# Pulleyboard.net
KiCad netlist of a schematic drawn in EAGLE
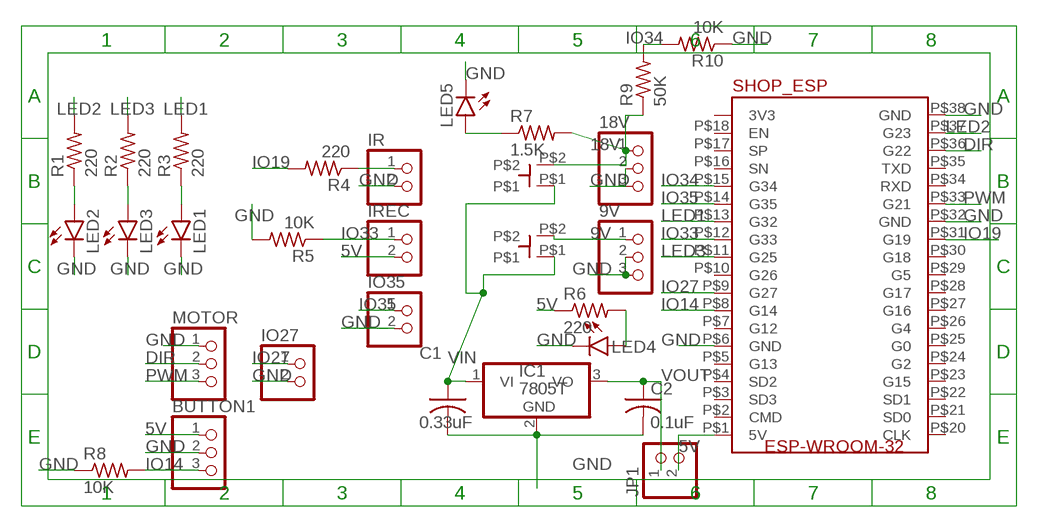
[diagram p0: schematic, sheet 1]

(export (version "E")
  (design (tool "Eeschema 10.0.6"))
  (components
    (comp (ref "9V")
      (value "PINHD-1X3")
      (footprint "eagle-import:1X03")
      (libsource (lib "eagle-import") (part "PINHD-1X3"))
    )
    (comp (ref "9VSW")
      (value "SWITCH")
      (footprint "eagle-import:SWTICH")
      (fields (field (name "SPICEPREFIX") "B"))
      (libsource (lib "eagle-import") (part "SWITCH"))
    )
    (comp (ref "18V")
      (value "PINHD-1X3")
      (footprint "eagle-import:1X03")
      (libsource (lib "eagle-import") (part "PINHD-1X3"))
    )
    (comp (ref "18VSW")
      (value "SWITCH")
      (footprint "eagle-import:SWTICH")
      (libsource (lib "eagle-import") (part "SWITCH"))
    )
    (comp (ref "BUTTON1")
      (value "PINHD-1X3")
      (footprint "eagle-import:1X03")
      (libsource (lib "eagle-import") (part "PINHD-1X3"))
    )
    (comp (ref "C1")
      (value "0.33uF")
      (footprint "eagle-import:C025-030X050")
      (libsource (lib "eagle-import") (part "C-US025-030X050"))
    )
    (comp (ref "C2")
      (value "0.1uF")
      (footprint "eagle-import:C025-030X050")
      (libsource (lib "eagle-import") (part "C-US025-030X050"))
    )
    (comp (ref "IC1")
      (value "7805T")
      (footprint "eagle-import:TO220H")
      (libsource (lib "eagle-import") (part "78T05"))
    )
    (comp (ref "IO27")
      (value "PINHD-1X2")
      (footprint "eagle-import:1X02")
      (libsource (lib "eagle-import") (part "PINHD-1X2"))
    )
    (comp (ref "IO35")
      (value "PINHD-1X2")
      (footprint "eagle-import:1X02")
      (libsource (lib "eagle-import") (part "PINHD-1X2"))
    )
    (comp (ref "IR")
      (value "PINHD-1X2")
      (footprint "eagle-import:1X02")
      (libsource (lib "eagle-import") (part "PINHD-1X2"))
    )
    (comp (ref "IREC")
      (value "PINHD-1X2")
      (footprint "eagle-import:1X02")
      (libsource (lib "eagle-import") (part "PINHD-1X2"))
    )
    (comp (ref "JP1")
      (value "PINHD-1X2")
      (footprint "eagle-import:1X02")
      (libsource (lib "eagle-import") (part "PINHD-1X2"))
    )
    (comp (ref "LED1")
      (value "LED5MM")
      (footprint "eagle-import:LED5MM")
      (libsource (lib "eagle-import") (part "ledbighole_LED5MM"))
    )
    (comp (ref "LED2")
      (value "LED5MM")
      (footprint "eagle-import:LED5MM")
      (libsource (lib "eagle-import") (part "ledbighole_LED5MM"))
    )
    (comp (ref "LED3")
      (value "LED5MM")
      (footprint "eagle-import:LED5MM")
      (libsource (lib "eagle-import") (part "ledbighole_LED5MM"))
    )
    (comp (ref "LED4")
      (value "LEDCHIPLED_1206")
      (footprint "eagle-import:CHIPLED_1206")
      (libsource (lib "eagle-import") (part "LEDCHIPLED_1206"))
    )
    (comp (ref "LED5")
      (value "LED5MM")
      (footprint "eagle-import:LED5MM")
      (libsource (lib "eagle-import") (part "ledbighole_LED5MM"))
    )
    (comp (ref "MOTOR")
      (value "PINHD-1X3")
      (footprint "eagle-import:1X03")
      (libsource (lib "eagle-import") (part "PINHD-1X3"))
    )
    (comp (ref "R1")
      (value "220")
      (footprint "eagle-import:R0805")
      (libsource (lib "eagle-import") (part "R-US_R0805"))
    )
    (comp (ref "R2")
      (value "220")
      (footprint "eagle-import:R0805")
      (libsource (lib "eagle-import") (part "R-US_R0805"))
    )
    (comp (ref "R3")
      (value "220")
      (footprint "eagle-import:R0805")
      (libsource (lib "eagle-import") (part "R-US_R0805"))
    )
    (comp (ref "R4")
      (value "220")
      (footprint "eagle-import:R0805")
      (libsource (lib "eagle-import") (part "R-US_R0805"))
    )
    (comp (ref "R5")
      (value "10K")
      (footprint "eagle-import:R0805")
      (libsource (lib "eagle-import") (part "R-US_R0805"))
    )
    (comp (ref "R6")
      (value "220")
      (footprint "eagle-import:R0805")
      (libsource (lib "eagle-import") (part "R-US_R0805"))
    )
    (comp (ref "R7")
      (value "1.5K")
      (footprint "eagle-import:R0805")
      (libsource (lib "eagle-import") (part "R-US_R0805"))
    )
    (comp (ref "R8")
      (value "10K")
      (footprint "eagle-import:R0805")
      (libsource (lib "eagle-import") (part "R-US_R0805"))
    )
    (comp (ref "R9")
      (value "50K")
      (footprint "eagle-import:R0805")
      (libsource (lib "eagle-import") (part "R-US_R0805"))
    )
    (comp (ref "R10")
      (value "10K")
      (footprint "eagle-import:R0805")
      (libsource (lib "eagle-import") (part "R-US_R0805"))
    )
    (comp (ref "U$3")
      (value "SHOP_ESP")
      (footprint "eagle-import:ESP32-WROOM-32")
      (libsource (lib "eagle-import") (part "SHOP_ESP"))
    )
  )
  (nets
    (net (code "1") (name "/3V3") (class "Default")
      (node (ref "U$3") (pin "P$19") (pinfunction "3V3_P$19") (pintype "power_in"))
    )
    (net (code "2") (name "/5V") (class "Default")
      (node (ref "BUTTON1") (pin "1") (pinfunction "1_1") (pintype "passive"))
      (node (ref "IREC") (pin "2") (pinfunction "2_2") (pintype "passive"))
      (node (ref "JP1") (pin "2") (pinfunction "2_2") (pintype "passive"))
      (node (ref "R6") (pin "1") (pinfunction "1_1") (pintype "passive"))
      (node (ref "U$3") (pin "P$1") (pinfunction "5V_P$1") (pintype "power_in"))
    )
    (net (code "3") (name "/9V") (class "Default")
      (node (ref "9V") (pin "1") (pinfunction "1_1") (pintype "passive"))
      (node (ref "9VSW") (pin "P$2") (pinfunction "P$2_P$2") (pintype "bidirectional"))
    )
    (net (code "4") (name "/18V") (class "Default")
      (node (ref "18V") (pin "1") (pinfunction "1_1") (pintype "passive"))
      (node (ref "18VSW") (pin "P$2") (pinfunction "P$2_P$2") (pintype "bidirectional"))
      (node (ref "R7") (pin "2") (pinfunction "2_2") (pintype "passive"))
      (node (ref "R9") (pin "1") (pinfunction "1_1") (pintype "passive"))
    )
    (net (code "5") (name "/CMD") (class "Default")
      (node (ref "U$3") (pin "P$2") (pinfunction "CMD_P$2") (pintype "power_in"))
    )
    (net (code "6") (name "/DIR") (class "Default")
      (node (ref "MOTOR") (pin "2") (pinfunction "2_2") (pintype "passive"))
      (node (ref "U$3") (pin "P$36") (pinfunction "G22_P$36") (pintype "bidirectional"))
    )
    (net (code "7") (name "/GND") (class "Default")
      (node (ref "18V") (pin "2") (pinfunction "2_2") (pintype "passive"))
      (node (ref "18V") (pin "3") (pinfunction "3_3") (pintype "passive"))
      (node (ref "9V") (pin "2") (pinfunction "2_2") (pintype "passive"))
      (node (ref "9V") (pin "3") (pinfunction "3_3") (pintype "passive"))
      (node (ref "BUTTON1") (pin "2") (pinfunction "2_2") (pintype "passive"))
      (node (ref "C1") (pin "2") (pinfunction "2_2") (pintype "passive"))
      (node (ref "C2") (pin "2") (pinfunction "2_2") (pintype "passive"))
      (node (ref "IC1") (pin "2") (pinfunction "GND_2") (pintype "passive"))
      (node (ref "IO27") (pin "2") (pinfunction "2_2") (pintype "passive"))
      (node (ref "IO35") (pin "2") (pinfunction "2_2") (pintype "passive"))
      (node (ref "IR") (pin "2") (pinfunction "2_2") (pintype "passive"))
      (node (ref "LED1") (pin "K") (pinfunction "C_K") (pintype "passive"))
      (node (ref "LED2") (pin "K") (pinfunction "C_K") (pintype "passive"))
      (node (ref "LED3") (pin "K") (pinfunction "C_K") (pintype "passive"))
      (node (ref "LED4") (pin "C") (pinfunction "C_C") (pintype "passive"))
      (node (ref "LED5") (pin "K") (pinfunction "C_K") (pintype "passive"))
      (node (ref "MOTOR") (pin "1") (pinfunction "1_1") (pintype "passive"))
      (node (ref "R10") (pin "1") (pinfunction "1_1") (pintype "passive"))
      (node (ref "R5") (pin "2") (pinfunction "2_2") (pintype "passive"))
      (node (ref "R8") (pin "1") (pinfunction "1_1") (pintype "passive"))
      (node (ref "U$3") (pin "P$32") (pinfunction "GND_P$32") (pintype "bidirectional"))
      (node (ref "U$3") (pin "P$38") (pinfunction "GND_P$38") (pintype "bidirectional"))
      (node (ref "U$3") (pin "P$6") (pinfunction "GND_P$6") (pintype "bidirectional"))
    )
    (net (code "8") (name "/IO14") (class "Default")
      (node (ref "BUTTON1") (pin "3") (pinfunction "3_3") (pintype "passive"))
      (node (ref "R8") (pin "2") (pinfunction "2_2") (pintype "passive"))
      (node (ref "U$3") (pin "P$8") (pinfunction "G14_P$8") (pintype "bidirectional"))
    )
    (net (code "9") (name "/IO19") (class "Default")
      (node (ref "R4") (pin "2") (pinfunction "2_2") (pintype "passive"))
      (node (ref "U$3") (pin "P$31") (pinfunction "G19_P$31") (pintype "bidirectional"))
    )
    (net (code "10") (name "/IO27") (class "Default")
      (node (ref "IO27") (pin "1") (pinfunction "1_1") (pintype "passive"))
      (node (ref "U$3") (pin "P$9") (pinfunction "G27_P$9") (pintype "bidirectional"))
    )
    (net (code "11") (name "/IO33") (class "Default")
      (node (ref "IREC") (pin "1") (pinfunction "1_1") (pintype "passive"))
      (node (ref "R5") (pin "1") (pinfunction "1_1") (pintype "passive"))
      (node (ref "U$3") (pin "P$12") (pinfunction "G33_P$12") (pintype "bidirectional"))
    )
    (net (code "12") (name "/IO34") (class "Default")
      (node (ref "R10") (pin "2") (pinfunction "2_2") (pintype "passive"))
      (node (ref "R9") (pin "2") (pinfunction "2_2") (pintype "passive"))
      (node (ref "U$3") (pin "P$15") (pinfunction "G34_P$15") (pintype "bidirectional"))
    )
    (net (code "13") (name "/IO35") (class "Default")
      (node (ref "IO35") (pin "1") (pinfunction "1_1") (pintype "passive"))
      (node (ref "U$3") (pin "P$14") (pinfunction "G35_P$14") (pintype "bidirectional"))
    )
    (net (code "14") (name "/LED1") (class "Default")
      (node (ref "R3") (pin "2") (pinfunction "2_2") (pintype "passive"))
      (node (ref "U$3") (pin "P$13") (pinfunction "G32_P$13") (pintype "bidirectional"))
    )
    (net (code "15") (name "/LED2") (class "Default")
      (node (ref "R1") (pin "2") (pinfunction "2_2") (pintype "passive"))
      (node (ref "U$3") (pin "P$37") (pinfunction "G23_P$37") (pintype "bidirectional"))
    )
    (net (code "16") (name "/LED3") (class "Default")
      (node (ref "R2") (pin "2") (pinfunction "2_2") (pintype "passive"))
      (node (ref "U$3") (pin "P$11") (pinfunction "G25_P$11") (pintype "bidirectional"))
    )
    (net (code "17") (name "/PWM") (class "Default")
      (node (ref "MOTOR") (pin "3") (pinfunction "3_3") (pintype "passive"))
      (node (ref "U$3") (pin "P$33") (pinfunction "G21_P$33") (pintype "bidirectional"))
    )
    (net (code "18") (name "/VIN") (class "Default")
      (node (ref "18VSW") (pin "P$1") (pinfunction "P$1_P$1") (pintype "bidirectional"))
      (node (ref "9VSW") (pin "P$1") (pinfunction "P$1_P$1") (pintype "bidirectional"))
      (node (ref "C1") (pin "1") (pinfunction "1_1") (pintype "passive"))
      (node (ref "IC1") (pin "1") (pinfunction "VI_1") (pintype "input"))
    )
    (net (code "19") (name "/VOUT") (class "Default")
      (node (ref "C2") (pin "1") (pinfunction "1_1") (pintype "passive"))
      (node (ref "IC1") (pin "3") (pinfunction "VO_3") (pintype "passive"))
      (node (ref "JP1") (pin "1") (pinfunction "1_1") (pintype "passive"))
    )
    (net (code "20") (name "Net-(IR-Pad1)") (class "Default")
      (node (ref "IR") (pin "1") (pinfunction "1_1") (pintype "passive"))
      (node (ref "R4") (pin "1") (pinfunction "1_1") (pintype "passive"))
    )
    (net (code "21") (name "Net-(LED1-PadA)") (class "Default")
      (node (ref "LED1") (pin "A") (pinfunction "A_A") (pintype "passive"))
      (node (ref "R3") (pin "1") (pinfunction "1_1") (pintype "passive"))
    )
    (net (code "22") (name "Net-(LED2-PadA)") (class "Default")
      (node (ref "LED2") (pin "A") (pinfunction "A_A") (pintype "passive"))
      (node (ref "R1") (pin "1") (pinfunction "1_1") (pintype "passive"))
    )
    (net (code "23") (name "Net-(LED3-PadA)") (class "Default")
      (node (ref "LED3") (pin "A") (pinfunction "A_A") (pintype "passive"))
      (node (ref "R2") (pin "1") (pinfunction "1_1") (pintype "passive"))
    )
    (net (code "24") (name "Net-(LED4-PadA)") (class "Default")
      (node (ref "LED4") (pin "A") (pinfunction "A_A") (pintype "passive"))
      (node (ref "R6") (pin "2") (pinfunction "2_2") (pintype "passive"))
    )
    (net (code "25") (name "Net-(LED5-PadA)") (class "Default")
      (node (ref "LED5") (pin "A") (pinfunction "A_A") (pintype "passive"))
      (node (ref "R7") (pin "1") (pinfunction "1_1") (pintype "passive"))
    )
    (net (code "26") (name "unconnected-(U$3-CLK-PadP$20)") (class "Default")
      (node (ref "U$3") (pin "P$20") (pinfunction "CLK_P$20") (pintype "bidirectional"))
    )
    (net (code "27") (name "unconnected-(U$3-EN-PadP$18)") (class "Default")
      (node (ref "U$3") (pin "P$18") (pinfunction "EN_P$18") (pintype "bidirectional"))
    )
    (net (code "28") (name "unconnected-(U$3-G0-PadP$25)") (class "Default")
      (node (ref "U$3") (pin "P$25") (pinfunction "G0_P$25") (pintype "bidirectional"))
    )
    (net (code "29") (name "unconnected-(U$3-G2-PadP$24)") (class "Default")
      (node (ref "U$3") (pin "P$24") (pinfunction "G2_P$24") (pintype "bidirectional"))
    )
    (net (code "30") (name "unconnected-(U$3-G4-PadP$26)") (class "Default")
      (node (ref "U$3") (pin "P$26") (pinfunction "G4_P$26") (pintype "bidirectional"))
    )
    (net (code "31") (name "unconnected-(U$3-G5-PadP$29)") (class "Default")
      (node (ref "U$3") (pin "P$29") (pinfunction "G5_P$29") (pintype "bidirectional"))
    )
    (net (code "32") (name "unconnected-(U$3-G12-PadP$7)") (class "Default")
      (node (ref "U$3") (pin "P$7") (pinfunction "G12_P$7") (pintype "bidirectional"))
    )
    (net (code "33") (name "unconnected-(U$3-G13-PadP$5)") (class "Default")
      (node (ref "U$3") (pin "P$5") (pinfunction "G13_P$5") (pintype "bidirectional"))
    )
    (net (code "34") (name "unconnected-(U$3-G15-PadP$23)") (class "Default")
      (node (ref "U$3") (pin "P$23") (pinfunction "G15_P$23") (pintype "bidirectional"))
    )
    (net (code "35") (name "unconnected-(U$3-G16-PadP$27)") (class "Default")
      (node (ref "U$3") (pin "P$27") (pinfunction "G16_P$27") (pintype "bidirectional"))
    )
    (net (code "36") (name "unconnected-(U$3-G17-PadP$28)") (class "Default")
      (node (ref "U$3") (pin "P$28") (pinfunction "G17_P$28") (pintype "bidirectional"))
    )
    (net (code "37") (name "unconnected-(U$3-G18-PadP$30)") (class "Default")
      (node (ref "U$3") (pin "P$30") (pinfunction "G18_P$30") (pintype "bidirectional"))
    )
    (net (code "38") (name "unconnected-(U$3-G26-PadP$10)") (class "Default")
      (node (ref "U$3") (pin "P$10") (pinfunction "G26_P$10") (pintype "bidirectional"))
    )
    (net (code "39") (name "unconnected-(U$3-RXD-PadP$34)") (class "Default")
      (node (ref "U$3") (pin "P$34") (pinfunction "RXD_P$34") (pintype "bidirectional"))
    )
    (net (code "40") (name "unconnected-(U$3-SD0-PadP$21)") (class "Default")
      (node (ref "U$3") (pin "P$21") (pinfunction "SD0_P$21") (pintype "bidirectional"))
    )
    (net (code "41") (name "unconnected-(U$3-SD1-PadP$22)") (class "Default")
      (node (ref "U$3") (pin "P$22") (pinfunction "SD1_P$22") (pintype "bidirectional"))
    )
    (net (code "42") (name "unconnected-(U$3-SD2-PadP$4)") (class "Default")
      (node (ref "U$3") (pin "P$4") (pinfunction "SD2_P$4") (pintype "bidirectional"))
    )
    (net (code "43") (name "unconnected-(U$3-SD3-PadP$3)") (class "Default")
      (node (ref "U$3") (pin "P$3") (pinfunction "SD3_P$3") (pintype "bidirectional"))
    )
    (net (code "44") (name "unconnected-(U$3-SN-PadP$16)") (class "Default")
      (node (ref "U$3") (pin "P$16") (pinfunction "SN_P$16") (pintype "bidirectional"))
    )
    (net (code "45") (name "unconnected-(U$3-SP-PadP$17)") (class "Default")
      (node (ref "U$3") (pin "P$17") (pinfunction "SP_P$17") (pintype "bidirectional"))
    )
    (net (code "46") (name "unconnected-(U$3-TXD-PadP$35)") (class "Default")
      (node (ref "U$3") (pin "P$35") (pinfunction "TXD_P$35") (pintype "bidirectional"))
    )
  )
)
